# Compressions_TOF_VLX6180_v1_3_1_mar2022.net
KiCad netlist of a schematic drawn in EAGLE
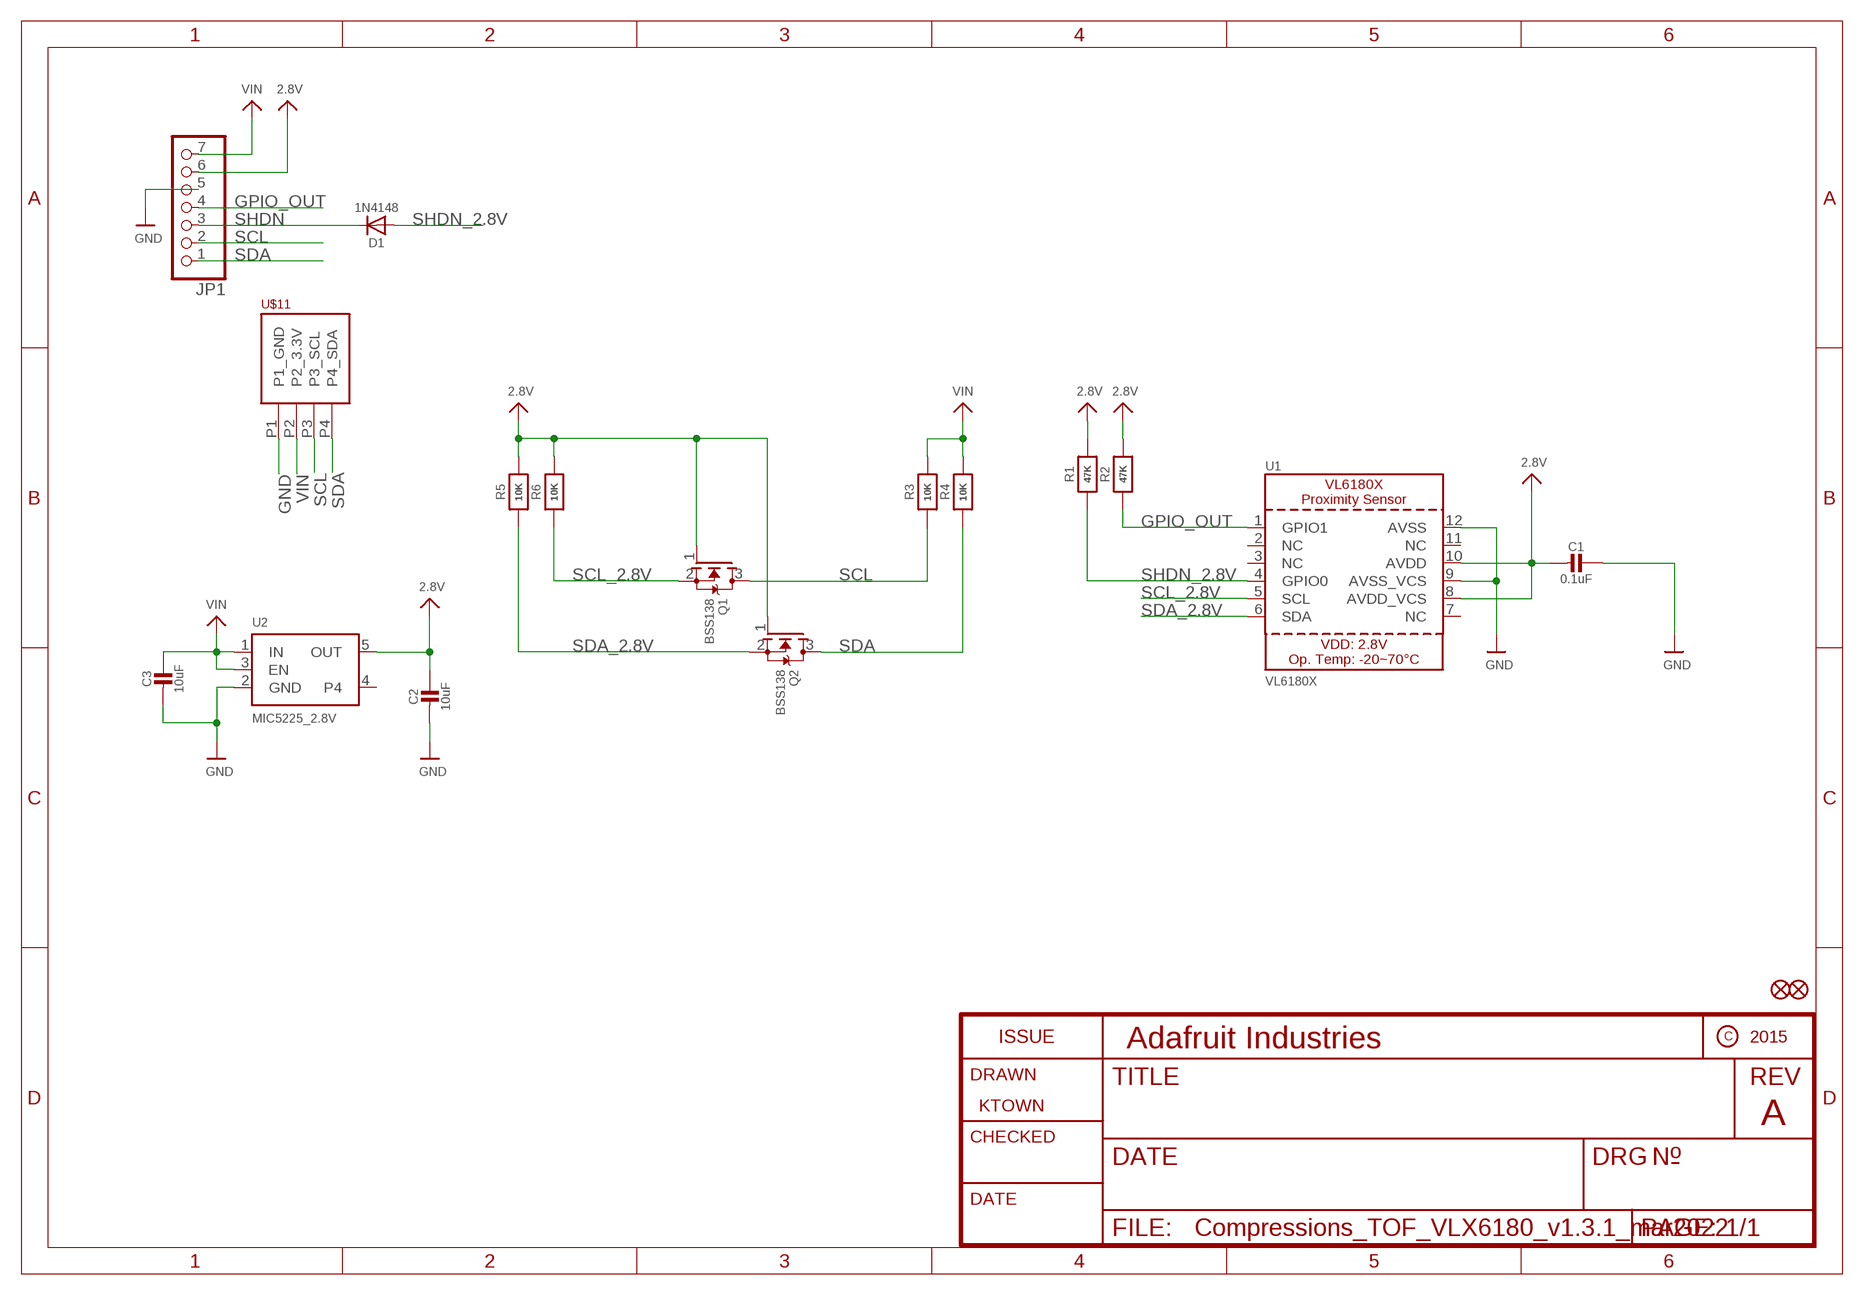
[diagram p0: schematic, sheet 1]

(export (version "E")
  (design (tool "Eeschema 10.0.6"))
  (components
    (comp (ref "C1")
      (value "0.1uF")
      (footprint "eagle-import:0805-NO")
      (libsource (lib "eagle-import") (part "CAP_CERAMIC0805-NOOUTLINE"))
    )
    (comp (ref "C2")
      (value "10uF")
      (footprint "eagle-import:0805-NO")
      (libsource (lib "eagle-import") (part "CAP_CERAMIC0805-NOOUTLINE"))
    )
    (comp (ref "C3")
      (value "10uF")
      (footprint "eagle-import:0805-NO")
      (libsource (lib "eagle-import") (part "CAP_CERAMIC0805-NOOUTLINE"))
    )
    (comp (ref "D1")
      (value "1N4148")
      (footprint "eagle-import:SOD-323")
      (libsource (lib "eagle-import") (part "DIODESOD-323"))
    )
    (comp (ref "FID1")
      (value "FIDUCIAL\"\"")
      (footprint "eagle-import:FIDUCIAL_1MM")
      (libsource (lib "eagle-import") (part "FIDUCIAL{dblquote}{dblquote}"))
    )
    (comp (ref "FID2")
      (value "FIDUCIAL\"\"")
      (footprint "eagle-import:FIDUCIAL_1MM")
      (libsource (lib "eagle-import") (part "FIDUCIAL{dblquote}{dblquote}"))
    )
    (comp (ref "JP1")
      (value "HEADER-1X770MIL")
      (footprint "eagle-import:1X07_ROUND_70")
      (libsource (lib "eagle-import") (part "HEADER-1X770MIL"))
    )
    (comp (ref "Q1")
      (value "BSS138")
      (footprint "eagle-import:SOT23-WIDE")
      (libsource (lib "eagle-import") (part "MOSFET-NWIDE"))
    )
    (comp (ref "Q2")
      (value "BSS138")
      (footprint "eagle-import:SOT23-WIDE")
      (libsource (lib "eagle-import") (part "MOSFET-NWIDE"))
    )
    (comp (ref "R1")
      (value "47K")
      (footprint "eagle-import:0805-NO")
      (libsource (lib "eagle-import") (part "RESISTOR0805_NOOUTLINE"))
    )
    (comp (ref "R2")
      (value "47K")
      (footprint "eagle-import:0805-NO")
      (libsource (lib "eagle-import") (part "RESISTOR0805_NOOUTLINE"))
    )
    (comp (ref "R3")
      (value "10K")
      (footprint "eagle-import:0805-NO")
      (libsource (lib "eagle-import") (part "RESISTOR0805_NOOUTLINE"))
    )
    (comp (ref "R4")
      (value "10K")
      (footprint "eagle-import:0805-NO")
      (libsource (lib "eagle-import") (part "RESISTOR0805_NOOUTLINE"))
    )
    (comp (ref "R5")
      (value "10K")
      (footprint "eagle-import:0805-NO")
      (libsource (lib "eagle-import") (part "RESISTOR0805_NOOUTLINE"))
    )
    (comp (ref "R6")
      (value "10K")
      (footprint "eagle-import:0805-NO")
      (libsource (lib "eagle-import") (part "RESISTOR0805_NOOUTLINE"))
    )
    (comp (ref "U$11")
      (value "PHOENIX_PTSM_M4_THANGLE")
      (footprint "eagle-import:PTSM_M4_TH")
      (libsource (lib "eagle-import") (part "PHOENIX_PTSM_M4_THANGLE"))
    )
    (comp (ref "U1")
      (value "VL6180X")
      (footprint "eagle-import:VL6180")
      (libsource (lib "eagle-import") (part "VL6180X"))
    )
    (comp (ref "U2")
      (value "MIC5225_2.8V")
      (footprint "eagle-import:SOT23-5")
      (libsource (lib "eagle-import") (part "VREG_SOT23-5"))
    )
  )
  (nets
    (net (code "1") (name "/GPIO_OUT") (class "Default")
      (node (ref "JP1") (pin "4") (pinfunction "4_4") (pintype "passive"))
      (node (ref "R2") (pin "1") (pinfunction "1_1") (pintype "passive"))
      (node (ref "U1") (pin "1") (pinfunction "GPIO1_1") (pintype "bidirectional"))
    )
    (net (code "2") (name "/SCL") (class "Default")
      (node (ref "JP1") (pin "2") (pinfunction "2_2") (pintype "passive"))
      (node (ref "Q1") (pin "3") (pinfunction "D_3") (pintype "bidirectional"))
      (node (ref "R3") (pin "1") (pinfunction "1_1") (pintype "passive"))
      (node (ref "U$11") (pin "P3") (pinfunction "P3_SCL_P3") (pintype "bidirectional"))
    )
    (net (code "3") (name "/SCL_2.8V") (class "Default")
      (node (ref "Q1") (pin "2") (pinfunction "S_2") (pintype "bidirectional"))
      (node (ref "R6") (pin "1") (pinfunction "1_1") (pintype "passive"))
      (node (ref "U1") (pin "5") (pinfunction "SCL_5") (pintype "input"))
    )
    (net (code "4") (name "/SDA") (class "Default")
      (node (ref "JP1") (pin "1") (pinfunction "1_1") (pintype "passive"))
      (node (ref "Q2") (pin "3") (pinfunction "D_3") (pintype "bidirectional"))
      (node (ref "R4") (pin "1") (pinfunction "1_1") (pintype "passive"))
      (node (ref "U$11") (pin "P4") (pinfunction "P4_SDA_P4") (pintype "bidirectional"))
    )
    (net (code "5") (name "/SDA_2.8V") (class "Default")
      (node (ref "Q2") (pin "2") (pinfunction "S_2") (pintype "bidirectional"))
      (node (ref "R5") (pin "1") (pinfunction "1_1") (pintype "passive"))
      (node (ref "U1") (pin "6") (pinfunction "SDA_6") (pintype "bidirectional"))
    )
    (net (code "6") (name "/SHDN") (class "Default")
      (node (ref "D1") (pin "C") (pinfunction "C_C") (pintype "passive"))
      (node (ref "JP1") (pin "3") (pinfunction "3_3") (pintype "passive"))
    )
    (net (code "7") (name "/SHDN_2.8V") (class "Default")
      (node (ref "D1") (pin "A") (pinfunction "A_A") (pintype "passive"))
      (node (ref "R1") (pin "1") (pinfunction "1_1") (pintype "passive"))
      (node (ref "U1") (pin "4") (pinfunction "GPIO0_4") (pintype "bidirectional"))
    )
    (net (code "8") (name "2.8V") (class "Default")
      (node (ref "C1") (pin "2") (pinfunction "2_2") (pintype "passive"))
      (node (ref "C2") (pin "1") (pinfunction "1_1") (pintype "passive"))
      (node (ref "JP1") (pin "6") (pinfunction "6_6") (pintype "passive"))
      (node (ref "Q1") (pin "1") (pinfunction "G_1") (pintype "bidirectional"))
      (node (ref "Q2") (pin "1") (pinfunction "G_1") (pintype "bidirectional"))
      (node (ref "R1") (pin "2") (pinfunction "2_2") (pintype "passive"))
      (node (ref "R2") (pin "2") (pinfunction "2_2") (pintype "passive"))
      (node (ref "R5") (pin "2") (pinfunction "2_2") (pintype "passive"))
      (node (ref "R6") (pin "2") (pinfunction "2_2") (pintype "passive"))
      (node (ref "U1") (pin "10") (pinfunction "AVDD_10") (pintype "power_in"))
      (node (ref "U1") (pin "8") (pinfunction "AVDD_VCS_8") (pintype "power_in"))
      (node (ref "U2") (pin "5") (pinfunction "OUT_5") (pintype "power_in"))
    )
    (net (code "9") (name "GND") (class "Default")
      (node (ref "C1") (pin "1") (pinfunction "1_1") (pintype "passive"))
      (node (ref "C2") (pin "2") (pinfunction "2_2") (pintype "passive"))
      (node (ref "C3") (pin "2") (pinfunction "2_2") (pintype "passive"))
      (node (ref "JP1") (pin "5") (pinfunction "5_5") (pintype "passive"))
      (node (ref "U$11") (pin "P1") (pinfunction "P1_GND_P1") (pintype "power_in"))
      (node (ref "U1") (pin "12") (pinfunction "AVSS_12") (pintype "power_in"))
      (node (ref "U1") (pin "9") (pinfunction "AVSS_VCS_9") (pintype "power_in"))
      (node (ref "U2") (pin "2") (pinfunction "GND_2") (pintype "power_in"))
    )
    (net (code "10") (name "VIN") (class "Default")
      (node (ref "C3") (pin "1") (pinfunction "1_1") (pintype "passive"))
      (node (ref "JP1") (pin "7") (pinfunction "7_7") (pintype "passive"))
      (node (ref "R3") (pin "2") (pinfunction "2_2") (pintype "passive"))
      (node (ref "R4") (pin "2") (pinfunction "2_2") (pintype "passive"))
      (node (ref "U$11") (pin "P2") (pinfunction "P2_3.3V_P2") (pintype "power_in"))
      (node (ref "U2") (pin "1") (pinfunction "IN_1") (pintype "power_in"))
      (node (ref "U2") (pin "3") (pinfunction "EN_3") (pintype "input"))
    )
    (net (code "11") (name "unconnected-(U1-NC-Pad2)") (class "Default")
      (node (ref "U1") (pin "2") (pinfunction "NC_2") (pintype "no_connect"))
    )
    (net (code "12") (name "unconnected-(U1-NC-Pad3)") (class "Default")
      (node (ref "U1") (pin "3") (pinfunction "NC_3") (pintype "no_connect"))
    )
    (net (code "13") (name "unconnected-(U1-NC-Pad7)") (class "Default")
      (node (ref "U1") (pin "7") (pinfunction "NC_7") (pintype "no_connect"))
    )
    (net (code "14") (name "unconnected-(U1-NC-Pad11)") (class "Default")
      (node (ref "U1") (pin "11") (pinfunction "NC_11") (pintype "no_connect"))
    )
    (net (code "15") (name "unconnected-(U2-P4-Pad4)") (class "Default")
      (node (ref "U2") (pin "4") (pinfunction "P4_4") (pintype "bidirectional"))
    )
  )
)
